# FPGAPower.net
KiCad netlist of a schematic drawn in Altium Designer
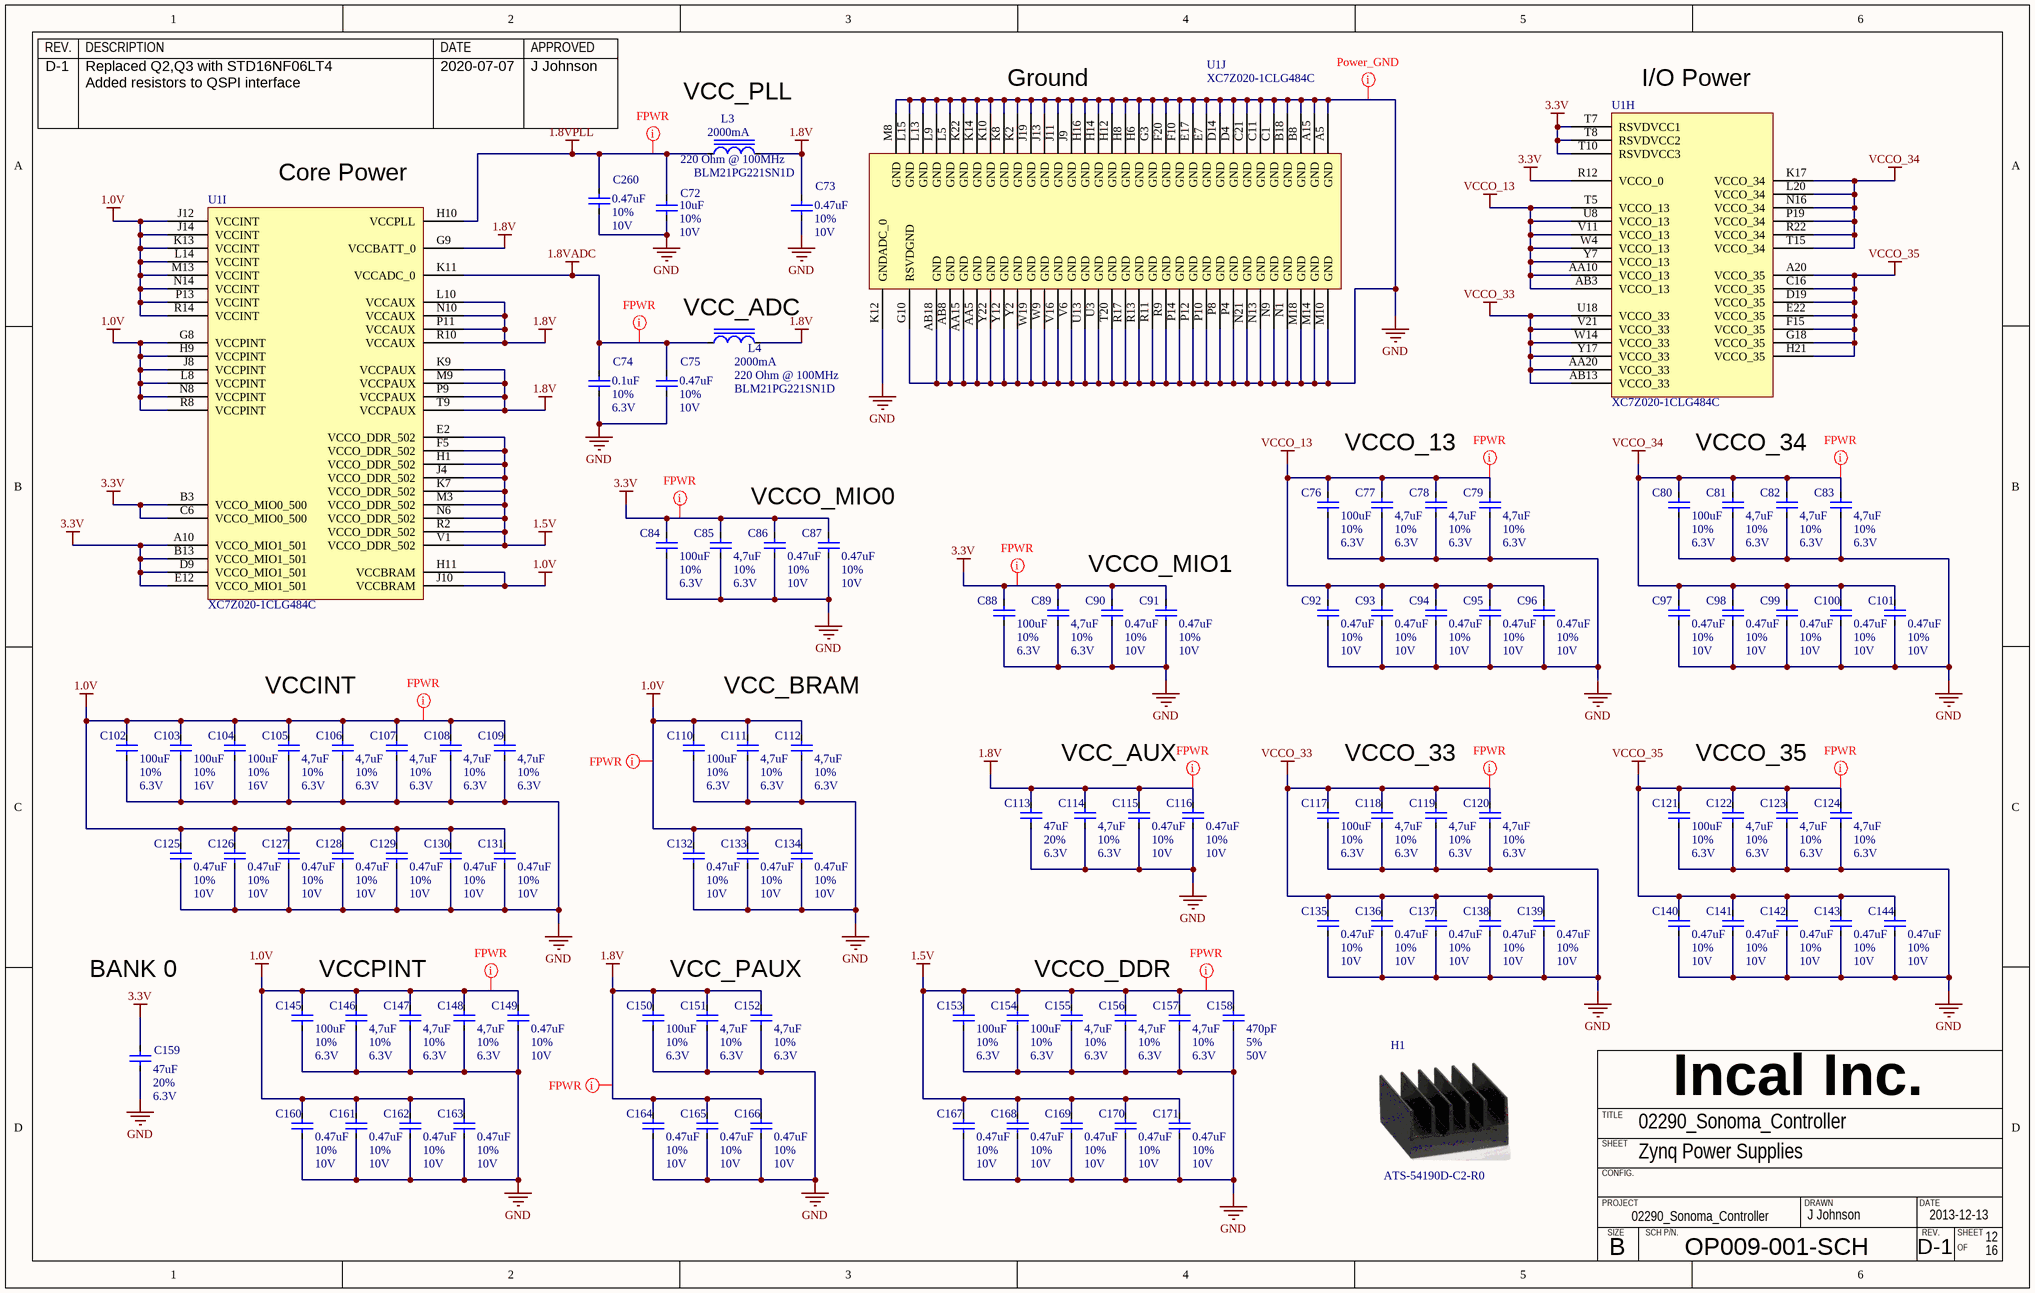
[diagram p0: FPGAPower.SchDoc]

(export (version "E")
  (design (tool "Eeschema 10.0.6"))
  (components
    (comp (ref "C72")
      (value "10uF")
      (footprint "CAPC1608X38N")
      (description "Capacitor ceramic, X5R, 10uF, 10V, 10%, -55 to +85 C, EIA0603")
      (fields
        (field (name "TOLERANCE") "10%")
        (field (name "VOLTAGE") "10V")
        (field (name "Comment") "CAPACITOR_NP_TYPE1")
      )
      (libsource (lib "parts") (part "CAPACITOR_NP_TYPE1"))
    )
    (comp (ref "C73")
      (value "0.47uF")
      (footprint "CAPC1005X55N")
      (description "Capacitor ceramic, X5R, 0.47uF, 10V, 10%, -55 to +85 C, EIA0402")
      (fields
        (field (name "TOLERANCE") "10%")
        (field (name "VOLTAGE") "10V")
        (field (name "Comment") "CAPACITOR_NP_TYPE1")
      )
      (libsource (lib "parts") (part "CAPACITOR_NP_TYPE1"))
    )
    (comp (ref "C74")
      (value "0.1uF")
      (footprint "CAPC0603X33N")
      (description "Capacitor ceramic, X5R, 0.1uF, 6.3V, 10%, -55 to +125 C, EIA0201")
      (fields
        (field (name "TOLERANCE") "10%")
        (field (name "VOLTAGE") "6.3V")
        (field (name "Comment") "CAPACITOR_NP_TYPE1")
      )
      (libsource (lib "parts") (part "CAPACITOR_NP_TYPE1"))
    )
    (comp (ref "C75")
      (value "0.47uF")
      (footprint "CAPC1005X55N")
      (description "Capacitor ceramic, X5R, 0.47uF, 10V, 10%, -55 to +85 C, EIA0402")
      (fields
        (field (name "TOLERANCE") "10%")
        (field (name "VOLTAGE") "10V")
        (field (name "Comment") "CAPACITOR_NP_TYPE1")
      )
      (libsource (lib "parts") (part "CAPACITOR_NP_TYPE1"))
    )
    (comp (ref "C76")
      (value "100uF")
      (footprint "CAPC3225X250N")
      (description "Capacitor ceramic, X5R, 100uF, 6.3V, 10%, -55 to +85 C, EIA1210")
      (fields
        (field (name "TOLERANCE") "10%")
        (field (name "VOLTAGE") "6.3V")
        (field (name "Comment") "CAPACITOR_NP_TYPE1")
      )
      (libsource (lib "parts") (part "CAPACITOR_NP_TYPE1"))
    )
    (comp (ref "C77")
      (value "4,7uF")
      (footprint "CAPC1005X33N")
      (description "Capacitor ceramic, X5R, 4,7uF, 6.3V, 10%, -55 to +85 C, EIA0402")
      (fields
        (field (name "TOLERANCE") "10%")
        (field (name "VOLTAGE") "6.3V")
        (field (name "Comment") "CAPACITOR_NP_TYPE1")
      )
      (libsource (lib "parts") (part "CAPACITOR_NP_TYPE1"))
    )
    (comp (ref "C78")
      (value "4,7uF")
      (footprint "CAPC1005X33N")
      (description "Capacitor ceramic, X5R, 4,7uF, 6.3V, 10%, -55 to +85 C, EIA0402")
      (fields
        (field (name "TOLERANCE") "10%")
        (field (name "VOLTAGE") "6.3V")
        (field (name "Comment") "CAPACITOR_NP_TYPE1")
      )
      (libsource (lib "parts") (part "CAPACITOR_NP_TYPE1"))
    )
    (comp (ref "C79")
      (value "4,7uF")
      (footprint "CAPC1005X33N")
      (description "Capacitor ceramic, X5R, 4,7uF, 6.3V, 10%, -55 to +85 C, EIA0402")
      (fields
        (field (name "TOLERANCE") "10%")
        (field (name "VOLTAGE") "6.3V")
        (field (name "Comment") "CAPACITOR_NP_TYPE1")
      )
      (libsource (lib "parts") (part "CAPACITOR_NP_TYPE1"))
    )
    (comp (ref "C80")
      (value "100uF")
      (footprint "CAPC3225X250N")
      (description "Capacitor ceramic, X5R, 100uF, 6.3V, 10%, -55 to +85 C, EIA1210")
      (fields
        (field (name "TOLERANCE") "10%")
        (field (name "VOLTAGE") "6.3V")
        (field (name "Comment") "CAPACITOR_NP_TYPE1")
      )
      (libsource (lib "parts") (part "CAPACITOR_NP_TYPE1"))
    )
    (comp (ref "C81")
      (value "4,7uF")
      (footprint "CAPC1005X33N")
      (description "Capacitor ceramic, X5R, 4,7uF, 6.3V, 10%, -55 to +85 C, EIA0402")
      (fields
        (field (name "TOLERANCE") "10%")
        (field (name "VOLTAGE") "6.3V")
        (field (name "Comment") "CAPACITOR_NP_TYPE1")
      )
      (libsource (lib "parts") (part "CAPACITOR_NP_TYPE1"))
    )
    (comp (ref "C82")
      (value "4,7uF")
      (footprint "CAPC1005X33N")
      (description "Capacitor ceramic, X5R, 4,7uF, 6.3V, 10%, -55 to +85 C, EIA0402")
      (fields
        (field (name "TOLERANCE") "10%")
        (field (name "VOLTAGE") "6.3V")
        (field (name "Comment") "CAPACITOR_NP_TYPE1")
      )
      (libsource (lib "parts") (part "CAPACITOR_NP_TYPE1"))
    )
    (comp (ref "C83")
      (value "4,7uF")
      (footprint "CAPC1005X33N")
      (description "Capacitor ceramic, X5R, 4,7uF, 6.3V, 10%, -55 to +85 C, EIA0402")
      (fields
        (field (name "TOLERANCE") "10%")
        (field (name "VOLTAGE") "6.3V")
        (field (name "Comment") "CAPACITOR_NP_TYPE1")
      )
      (libsource (lib "parts") (part "CAPACITOR_NP_TYPE1"))
    )
    (comp (ref "C84")
      (value "100uF")
      (footprint "CAPC3225X250N")
      (description "Capacitor ceramic, X5R, 100uF, 6.3V, 10%, -55 to +85 C, EIA1210")
      (fields
        (field (name "TOLERANCE") "10%")
        (field (name "VOLTAGE") "6.3V")
        (field (name "Comment") "CAPACITOR_NP_TYPE1")
      )
      (libsource (lib "parts") (part "CAPACITOR_NP_TYPE1"))
    )
    (comp (ref "C85")
      (value "4,7uF")
      (footprint "CAPC1005X33N")
      (description "Capacitor ceramic, X5R, 4,7uF, 6.3V, 10%, -55 to +85 C, EIA0402")
      (fields
        (field (name "TOLERANCE") "10%")
        (field (name "VOLTAGE") "6.3V")
        (field (name "Comment") "CAPACITOR_NP_TYPE1")
      )
      (libsource (lib "parts") (part "CAPACITOR_NP_TYPE1"))
    )
    (comp (ref "C86")
      (value "0.47uF")
      (footprint "CAPC1005X55N")
      (description "Capacitor ceramic, X5R, 0.47uF, 10V, 10%, -55 to +85 C, EIA0402")
      (fields
        (field (name "TOLERANCE") "10%")
        (field (name "VOLTAGE") "10V")
        (field (name "Comment") "CAPACITOR_NP_TYPE1")
      )
      (libsource (lib "parts") (part "CAPACITOR_NP_TYPE1"))
    )
    (comp (ref "C87")
      (value "0.47uF")
      (footprint "CAPC1005X55N")
      (description "Capacitor ceramic, X5R, 0.47uF, 10V, 10%, -55 to +85 C, EIA0402")
      (fields
        (field (name "TOLERANCE") "10%")
        (field (name "VOLTAGE") "10V")
        (field (name "Comment") "CAPACITOR_NP_TYPE1")
      )
      (libsource (lib "parts") (part "CAPACITOR_NP_TYPE1"))
    )
    (comp (ref "C88")
      (value "100uF")
      (footprint "CAPC3225X250N")
      (description "Capacitor ceramic, X5R, 100uF, 6.3V, 10%, -55 to +85 C, EIA1210")
      (fields
        (field (name "TOLERANCE") "10%")
        (field (name "VOLTAGE") "6.3V")
        (field (name "Comment") "CAPACITOR_NP_TYPE1")
      )
      (libsource (lib "parts") (part "CAPACITOR_NP_TYPE1"))
    )
    (comp (ref "C89")
      (value "4,7uF")
      (footprint "CAPC1005X33N")
      (description "Capacitor ceramic, X5R, 4,7uF, 6.3V, 10%, -55 to +85 C, EIA0402")
      (fields
        (field (name "TOLERANCE") "10%")
        (field (name "VOLTAGE") "6.3V")
        (field (name "Comment") "CAPACITOR_NP_TYPE1")
      )
      (libsource (lib "parts") (part "CAPACITOR_NP_TYPE1"))
    )
    (comp (ref "C90")
      (value "0.47uF")
      (footprint "CAPC1005X55N")
      (description "Capacitor ceramic, X5R, 0.47uF, 10V, 10%, -55 to +85 C, EIA0402")
      (fields
        (field (name "TOLERANCE") "10%")
        (field (name "VOLTAGE") "10V")
        (field (name "Comment") "CAPACITOR_NP_TYPE1")
      )
      (libsource (lib "parts") (part "CAPACITOR_NP_TYPE1"))
    )
    (comp (ref "C91")
      (value "0.47uF")
      (footprint "CAPC1005X55N")
      (description "Capacitor ceramic, X5R, 0.47uF, 10V, 10%, -55 to +85 C, EIA0402")
      (fields
        (field (name "TOLERANCE") "10%")
        (field (name "VOLTAGE") "10V")
        (field (name "Comment") "CAPACITOR_NP_TYPE1")
      )
      (libsource (lib "parts") (part "CAPACITOR_NP_TYPE1"))
    )
    (comp (ref "C92")
      (value "0.47uF")
      (footprint "CAPC1005X55N")
      (description "Capacitor ceramic, X5R, 0.47uF, 10V, 10%, -55 to +85 C, EIA0402")
      (fields
        (field (name "TOLERANCE") "10%")
        (field (name "VOLTAGE") "10V")
        (field (name "Comment") "CAPACITOR_NP_TYPE1")
      )
      (libsource (lib "parts") (part "CAPACITOR_NP_TYPE1"))
    )
    (comp (ref "C93")
      (value "0.47uF")
      (footprint "CAPC1005X55N")
      (description "Capacitor ceramic, X5R, 0.47uF, 10V, 10%, -55 to +85 C, EIA0402")
      (fields
        (field (name "TOLERANCE") "10%")
        (field (name "VOLTAGE") "10V")
        (field (name "Comment") "CAPACITOR_NP_TYPE1")
      )
      (libsource (lib "parts") (part "CAPACITOR_NP_TYPE1"))
    )
    (comp (ref "C94")
      (value "0.47uF")
      (footprint "CAPC1005X55N")
      (description "Capacitor ceramic, X5R, 0.47uF, 10V, 10%, -55 to +85 C, EIA0402")
      (fields
        (field (name "TOLERANCE") "10%")
        (field (name "VOLTAGE") "10V")
        (field (name "Comment") "CAPACITOR_NP_TYPE1")
      )
      (libsource (lib "parts") (part "CAPACITOR_NP_TYPE1"))
    )
    (comp (ref "C95")
      (value "0.47uF")
      (footprint "CAPC1005X55N")
      (description "Capacitor ceramic, X5R, 0.47uF, 10V, 10%, -55 to +85 C, EIA0402")
      (fields
        (field (name "TOLERANCE") "10%")
        (field (name "VOLTAGE") "10V")
        (field (name "Comment") "CAPACITOR_NP_TYPE1")
      )
      (libsource (lib "parts") (part "CAPACITOR_NP_TYPE1"))
    )
    (comp (ref "C96")
      (value "0.47uF")
      (footprint "CAPC1005X55N")
      (description "Capacitor ceramic, X5R, 0.47uF, 10V, 10%, -55 to +85 C, EIA0402")
      (fields
        (field (name "TOLERANCE") "10%")
        (field (name "VOLTAGE") "10V")
        (field (name "Comment") "CAPACITOR_NP_TYPE1")
      )
      (libsource (lib "parts") (part "CAPACITOR_NP_TYPE1"))
    )
    (comp (ref "C97")
      (value "0.47uF")
      (footprint "CAPC1005X55N")
      (description "Capacitor ceramic, X5R, 0.47uF, 10V, 10%, -55 to +85 C, EIA0402")
      (fields
        (field (name "TOLERANCE") "10%")
        (field (name "VOLTAGE") "10V")
        (field (name "Comment") "CAPACITOR_NP_TYPE1")
      )
      (libsource (lib "parts") (part "CAPACITOR_NP_TYPE1"))
    )
    (comp (ref "C98")
      (value "0.47uF")
      (footprint "CAPC1005X55N")
      (description "Capacitor ceramic, X5R, 0.47uF, 10V, 10%, -55 to +85 C, EIA0402")
      (fields
        (field (name "TOLERANCE") "10%")
        (field (name "VOLTAGE") "10V")
        (field (name "Comment") "CAPACITOR_NP_TYPE1")
      )
      (libsource (lib "parts") (part "CAPACITOR_NP_TYPE1"))
    )
    (comp (ref "C99")
      (value "0.47uF")
      (footprint "CAPC1005X55N")
      (description "Capacitor ceramic, X5R, 0.47uF, 10V, 10%, -55 to +85 C, EIA0402")
      (fields
        (field (name "TOLERANCE") "10%")
        (field (name "VOLTAGE") "10V")
        (field (name "Comment") "CAPACITOR_NP_TYPE1")
      )
      (libsource (lib "parts") (part "CAPACITOR_NP_TYPE1"))
    )
    (comp (ref "C100")
      (value "0.47uF")
      (footprint "CAPC1005X55N")
      (description "Capacitor ceramic, X5R, 0.47uF, 10V, 10%, -55 to +85 C, EIA0402")
      (fields
        (field (name "TOLERANCE") "10%")
        (field (name "VOLTAGE") "10V")
        (field (name "Comment") "CAPACITOR_NP_TYPE1")
      )
      (libsource (lib "parts") (part "CAPACITOR_NP_TYPE1"))
    )
    (comp (ref "C101")
      (value "0.47uF")
      (footprint "CAPC1005X55N")
      (description "Capacitor ceramic, X5R, 0.47uF, 10V, 10%, -55 to +85 C, EIA0402")
      (fields
        (field (name "TOLERANCE") "10%")
        (field (name "VOLTAGE") "10V")
        (field (name "Comment") "CAPACITOR_NP_TYPE1")
      )
      (libsource (lib "parts") (part "CAPACITOR_NP_TYPE1"))
    )
    (comp (ref "C102")
      (value "100uF")
      (footprint "CAPC3225X250N")
      (description "Capacitor ceramic, X5R, 100uF, 6.3V, 10%, -55 to +85 C, EIA1210")
      (fields
        (field (name "TOLERANCE") "10%")
        (field (name "VOLTAGE") "6.3V")
        (field (name "Comment") "CAPACITOR_NP_TYPE1")
      )
      (libsource (lib "parts") (part "CAPACITOR_NP_TYPE1"))
    )
    (comp (ref "C103")
      (value "100uF")
      (footprint "CAPC3225X250N")
      (description "Capacitor ceramic, X5R, 100uF, 16V, 10%, -55 to +85 C, EIA1210")
      (fields
        (field (name "TOLERANCE") "10%")
        (field (name "VOLTAGE") "16V")
        (field (name "Comment") "CAPACITOR_NP_TYPE1")
      )
      (libsource (lib "parts") (part "CAPACITOR_NP_TYPE1"))
    )
    (comp (ref "C104")
      (value "100uF")
      (footprint "CAPC3225X250N")
      (description "Capacitor ceramic, X5R, 100uF, 16V, 10%, -55 to +85 C, EIA1210")
      (fields
        (field (name "TOLERANCE") "10%")
        (field (name "VOLTAGE") "16V")
        (field (name "Comment") "CAPACITOR_NP_TYPE1")
      )
      (libsource (lib "parts") (part "CAPACITOR_NP_TYPE1"))
    )
    (comp (ref "C105")
      (value "4,7uF")
      (footprint "CAPC1005X33N")
      (description "Capacitor ceramic, X5R, 4,7uF, 6.3V, 10%, -55 to +85 C, EIA0402")
      (fields
        (field (name "TOLERANCE") "10%")
        (field (name "VOLTAGE") "6.3V")
        (field (name "Comment") "CAPACITOR_NP_TYPE1")
      )
      (libsource (lib "parts") (part "CAPACITOR_NP_TYPE1"))
    )
    (comp (ref "C106")
      (value "4,7uF")
      (footprint "CAPC1005X33N")
      (description "Capacitor ceramic, X5R, 4,7uF, 6.3V, 10%, -55 to +85 C, EIA0402")
      (fields
        (field (name "TOLERANCE") "10%")
        (field (name "VOLTAGE") "6.3V")
        (field (name "Comment") "CAPACITOR_NP_TYPE1")
      )
      (libsource (lib "parts") (part "CAPACITOR_NP_TYPE1"))
    )
    (comp (ref "C107")
      (value "4,7uF")
      (footprint "CAPC1005X33N")
      (description "Capacitor ceramic, X5R, 4,7uF, 6.3V, 10%, -55 to +85 C, EIA0402")
      (fields
        (field (name "TOLERANCE") "10%")
        (field (name "VOLTAGE") "6.3V")
        (field (name "Comment") "CAPACITOR_NP_TYPE1")
      )
      (libsource (lib "parts") (part "CAPACITOR_NP_TYPE1"))
    )
    (comp (ref "C108")
      (value "4,7uF")
      (footprint "CAPC1005X33N")
      (description "Capacitor ceramic, X5R, 4,7uF, 6.3V, 10%, -55 to +85 C, EIA0402")
      (fields
        (field (name "TOLERANCE") "10%")
        (field (name "VOLTAGE") "6.3V")
        (field (name "Comment") "CAPACITOR_NP_TYPE1")
      )
      (libsource (lib "parts") (part "CAPACITOR_NP_TYPE1"))
    )
    (comp (ref "C109")
      (value "4,7uF")
      (footprint "CAPC1005X33N")
      (description "Capacitor ceramic, X5R, 4,7uF, 6.3V, 10%, -55 to +85 C, EIA0402")
      (fields
        (field (name "TOLERANCE") "10%")
        (field (name "VOLTAGE") "6.3V")
        (field (name "Comment") "CAPACITOR_NP_TYPE1")
      )
      (libsource (lib "parts") (part "CAPACITOR_NP_TYPE1"))
    )
    (comp (ref "C110")
      (value "100uF")
      (footprint "CAPC3225X250N")
      (description "Capacitor ceramic, X5R, 100uF, 6.3V, 10%, -55 to +85 C, EIA1210")
      (fields
        (field (name "TOLERANCE") "10%")
        (field (name "VOLTAGE") "6.3V")
        (field (name "Comment") "CAPACITOR_NP_TYPE1")
      )
      (libsource (lib "parts") (part "CAPACITOR_NP_TYPE1"))
    )
    (comp (ref "C111")
      (value "4,7uF")
      (footprint "CAPC1005X33N")
      (description "Capacitor ceramic, X5R, 4,7uF, 6.3V, 10%, -55 to +85 C, EIA0402")
      (fields
        (field (name "TOLERANCE") "10%")
        (field (name "VOLTAGE") "6.3V")
        (field (name "Comment") "CAPACITOR_NP_TYPE1")
      )
      (libsource (lib "parts") (part "CAPACITOR_NP_TYPE1"))
    )
    (comp (ref "C112")
      (value "4,7uF")
      (footprint "CAPC1005X33N")
      (description "Capacitor ceramic, X5R, 4,7uF, 6.3V, 10%, -55 to +85 C, EIA0402")
      (fields
        (field (name "TOLERANCE") "10%")
        (field (name "VOLTAGE") "6.3V")
        (field (name "Comment") "CAPACITOR_NP_TYPE1")
      )
      (libsource (lib "parts") (part "CAPACITOR_NP_TYPE1"))
    )
    (comp (ref "C113")
      (value "47uF")
      (footprint "CAPC2013X125N")
      (description "Capacitor ceramic, X5R, 47uF, 6.3V, 20%, -55 to +85 C,")
      (fields
        (field (name "TOLERANCE") "20%")
        (field (name "VOLTAGE") "6.3V")
        (field (name "Comment") "CAPACITOR_NP_TYPE1")
      )
      (libsource (lib "parts") (part "CAPACITOR_NP_TYPE1"))
    )
    (comp (ref "C114")
      (value "4,7uF")
      (footprint "CAPC1005X33N")
      (description "Capacitor ceramic, X5R, 4,7uF, 6.3V, 10%, -55 to +85 C, EIA0402")
      (fields
        (field (name "TOLERANCE") "10%")
        (field (name "VOLTAGE") "6.3V")
        (field (name "Comment") "CAPACITOR_NP_TYPE1")
      )
      (libsource (lib "parts") (part "CAPACITOR_NP_TYPE1"))
    )
    (comp (ref "C115")
      (value "0.47uF")
      (footprint "CAPC1005X55N")
      (description "Capacitor ceramic, X5R, 0.47uF, 10V, 10%, -55 to +85 C, EIA0402")
      (fields
        (field (name "TOLERANCE") "10%")
        (field (name "VOLTAGE") "10V")
        (field (name "Comment") "CAPACITOR_NP_TYPE1")
      )
      (libsource (lib "parts") (part "CAPACITOR_NP_TYPE1"))
    )
    (comp (ref "C116")
      (value "0.47uF")
      (footprint "CAPC1005X55N")
      (description "Capacitor ceramic, X5R, 0.47uF, 10V, 10%, -55 to +85 C, EIA0402")
      (fields
        (field (name "TOLERANCE") "10%")
        (field (name "VOLTAGE") "10V")
        (field (name "Comment") "CAPACITOR_NP_TYPE1")
      )
      (libsource (lib "parts") (part "CAPACITOR_NP_TYPE1"))
    )
    (comp (ref "C117")
      (value "100uF")
      (footprint "CAPC3225X250N")
      (description "Capacitor ceramic, X5R, 100uF, 6.3V, 10%, -55 to +85 C, EIA1210")
      (fields
        (field (name "TOLERANCE") "10%")
        (field (name "VOLTAGE") "6.3V")
        (field (name "Comment") "CAPACITOR_NP_TYPE1")
      )
      (libsource (lib "parts") (part "CAPACITOR_NP_TYPE1"))
    )
    (comp (ref "C118")
      (value "4,7uF")
      (footprint "CAPC1005X33N")
      (description "Capacitor ceramic, X5R, 4,7uF, 6.3V, 10%, -55 to +85 C, EIA0402")
      (fields
        (field (name "TOLERANCE") "10%")
        (field (name "VOLTAGE") "6.3V")
        (field (name "Comment") "CAPACITOR_NP_TYPE1")
      )
      (libsource (lib "parts") (part "CAPACITOR_NP_TYPE1"))
    )
    (comp (ref "C119")
      (value "4,7uF")
      (footprint "CAPC1005X33N")
      (description "Capacitor ceramic, X5R, 4,7uF, 6.3V, 10%, -55 to +85 C, EIA0402")
      (fields
        (field (name "TOLERANCE") "10%")
        (field (name "VOLTAGE") "6.3V")
        (field (name "Comment") "CAPACITOR_NP_TYPE1")
      )
      (libsource (lib "parts") (part "CAPACITOR_NP_TYPE1"))
    )
    (comp (ref "C120")
      (value "4,7uF")
      (footprint "CAPC1005X33N")
      (description "Capacitor ceramic, X5R, 4,7uF, 6.3V, 10%, -55 to +85 C, EIA0402")
      (fields
        (field (name "TOLERANCE") "10%")
        (field (name "VOLTAGE") "6.3V")
        (field (name "Comment") "CAPACITOR_NP_TYPE1")
      )
      (libsource (lib "parts") (part "CAPACITOR_NP_TYPE1"))
    )
    (comp (ref "C121")
      (value "100uF")
      (footprint "CAPC3225X250N")
      (description "Capacitor ceramic, X5R, 100uF, 6.3V, 10%, -55 to +85 C, EIA1210")
      (fields
        (field (name "TOLERANCE") "10%")
        (field (name "VOLTAGE") "6.3V")
        (field (name "Comment") "CAPACITOR_NP_TYPE1")
      )
      (libsource (lib "parts") (part "CAPACITOR_NP_TYPE1"))
    )
    (comp (ref "C122")
      (value "4,7uF")
      (footprint "CAPC1005X33N")
      (description "Capacitor ceramic, X5R, 4,7uF, 6.3V, 10%, -55 to +85 C, EIA0402")
      (fields
        (field (name "TOLERANCE") "10%")
        (field (name "VOLTAGE") "6.3V")
        (field (name "Comment") "CAPACITOR_NP_TYPE1")
      )
      (libsource (lib "parts") (part "CAPACITOR_NP_TYPE1"))
    )
    (comp (ref "C123")
      (value "4,7uF")
      (footprint "CAPC1005X33N")
      (description "Capacitor ceramic, X5R, 4,7uF, 6.3V, 10%, -55 to +85 C, EIA0402")
      (fields
        (field (name "TOLERANCE") "10%")
        (field (name "VOLTAGE") "6.3V")
        (field (name "Comment") "CAPACITOR_NP_TYPE1")
      )
      (libsource (lib "parts") (part "CAPACITOR_NP_TYPE1"))
    )
    (comp (ref "C124")
      (value "4,7uF")
      (footprint "CAPC1005X33N")
      (description "Capacitor ceramic, X5R, 4,7uF, 6.3V, 10%, -55 to +85 C, EIA0402")
      (fields
        (field (name "TOLERANCE") "10%")
        (field (name "VOLTAGE") "6.3V")
        (field (name "Comment") "CAPACITOR_NP_TYPE1")
      )
      (libsource (lib "parts") (part "CAPACITOR_NP_TYPE1"))
    )
    (comp (ref "C125")
      (value "0.47uF")
      (footprint "CAPC1005X55N")
      (description "Capacitor ceramic, X5R, 0.47uF, 10V, 10%, -55 to +85 C, EIA0402")
      (fields
        (field (name "TOLERANCE") "10%")
        (field (name "VOLTAGE") "10V")
        (field (name "Comment") "CAPACITOR_NP_TYPE1")
      )
      (libsource (lib "parts") (part "CAPACITOR_NP_TYPE1"))
    )
    (comp (ref "C126")
      (value "0.47uF")
      (footprint "CAPC1005X55N")
      (description "Capacitor ceramic, X5R, 0.47uF, 10V, 10%, -55 to +85 C, EIA0402")
      (fields
        (field (name "TOLERANCE") "10%")
        (field (name "VOLTAGE") "10V")
        (field (name "Comment") "CAPACITOR_NP_TYPE1")
      )
      (libsource (lib "parts") (part "CAPACITOR_NP_TYPE1"))
    )
    (comp (ref "C127")
      (value "0.47uF")
      (footprint "CAPC1005X55N")
      (description "Capacitor ceramic, X5R, 0.47uF, 10V, 10%, -55 to +85 C, EIA0402")
      (fields
        (field (name "TOLERANCE") "10%")
        (field (name "VOLTAGE") "10V")
        (field (name "Comment") "CAPACITOR_NP_TYPE1")
      )
      (libsource (lib "parts") (part "CAPACITOR_NP_TYPE1"))
    )
    (comp (ref "C128")
      (value "0.47uF")
      (footprint "CAPC1005X55N")
      (description "Capacitor ceramic, X5R, 0.47uF, 10V, 10%, -55 to +85 C, EIA0402")
      (fields
        (field (name "TOLERANCE") "10%")
        (field (name "VOLTAGE") "10V")
        (field (name "Comment") "CAPACITOR_NP_TYPE1")
      )
      (libsource (lib "parts") (part "CAPACITOR_NP_TYPE1"))
    )
    (comp (ref "C129")
      (value "0.47uF")
      (footprint "CAPC1005X55N")
      (description "Capacitor ceramic, X5R, 0.47uF, 10V, 10%, -55 to +85 C, EIA0402")
      (fields
        (field (name "TOLERANCE") "10%")
        (field (name "VOLTAGE") "10V")
        (field (name "Comment") "CAPACITOR_NP_TYPE1")
      )
      (libsource (lib "parts") (part "CAPACITOR_NP_TYPE1"))
    )
    (comp (ref "C130")
      (value "0.47uF")
      (footprint "CAPC1005X55N")
      (description "Capacitor ceramic, X5R, 0.47uF, 10V, 10%, -55 to +85 C, EIA0402")
      (fields
        (field (name "TOLERANCE") "10%")
        (field (name "VOLTAGE") "10V")
        (field (name "Comment") "CAPACITOR_NP_TYPE1")
      )
      (libsource (lib "parts") (part "CAPACITOR_NP_TYPE1"))
    )
    (comp (ref "C131")
      (value "0.47uF")
      (footprint "CAPC1005X55N")
      (description "Capacitor ceramic, X5R, 0.47uF, 10V, 10%, -55 to +85 C, EIA0402")
      (fields
        (field (name "TOLERANCE") "10%")
        (field (name "VOLTAGE") "10V")
        (field (name "Comment") "CAPACITOR_NP_TYPE1")
      )
      (libsource (lib "parts") (part "CAPACITOR_NP_TYPE1"))
    )
    (comp (ref "C132")
      (value "0.47uF")
      (footprint "CAPC1005X55N")
      (description "Capacitor ceramic, X5R, 0.47uF, 10V, 10%, -55 to +85 C, EIA0402")
      (fields
        (field (name "TOLERANCE") "10%")
        (field (name "VOLTAGE") "10V")
        (field (name "Comment") "CAPACITOR_NP_TYPE1")
      )
      (libsource (lib "parts") (part "CAPACITOR_NP_TYPE1"))
    )
    (comp (ref "C133")
      (value "0.47uF")
      (footprint "CAPC1005X55N")
      (description "Capacitor ceramic, X5R, 0.47uF, 10V, 10%, -55 to +85 C, EIA0402")
      (fields
        (field (name "TOLERANCE") "10%")
        (field (name "VOLTAGE") "10V")
        (field (name "Comment") "CAPACITOR_NP_TYPE1")
      )
      (libsource (lib "parts") (part "CAPACITOR_NP_TYPE1"))
    )
    (comp (ref "C134")
      (value "0.47uF")
      (footprint "CAPC1005X55N")
      (description "Capacitor ceramic, X5R, 0.47uF, 10V, 10%, -55 to +85 C, EIA0402")
      (fields
        (field (name "TOLERANCE") "10%")
        (field (name "VOLTAGE") "10V")
        (field (name "Comment") "CAPACITOR_NP_TYPE1")
      )
      (libsource (lib "parts") (part "CAPACITOR_NP_TYPE1"))
    )
    (comp (ref "C135")
      (value "0.47uF")
      (footprint "CAPC1005X55N")
      (description "Capacitor ceramic, X5R, 0.47uF, 10V, 10%, -55 to +85 C, EIA0402")
      (fields
        (field (name "TOLERANCE") "10%")
        (field (name "VOLTAGE") "10V")
        (field (name "Comment") "CAPACITOR_NP_TYPE1")
      )
      (libsource (lib "parts") (part "CAPACITOR_NP_TYPE1"))
    )
    (comp (ref "C136")
      (value "0.47uF")
      (footprint "CAPC1005X55N")
      (description "Capacitor ceramic, X5R, 0.47uF, 10V, 10%, -55 to +85 C, EIA0402")
      (fields
        (field (name "TOLERANCE") "10%")
        (field (name "VOLTAGE") "10V")
        (field (name "Comment") "CAPACITOR_NP_TYPE1")
      )
      (libsource (lib "parts") (part "CAPACITOR_NP_TYPE1"))
    )
    (comp (ref "C137")
      (value "0.47uF")
      (footprint "CAPC1005X55N")
      (description "Capacitor ceramic, X5R, 0.47uF, 10V, 10%, -55 to +85 C, EIA0402")
      (fields
        (field (name "TOLERANCE") "10%")
        (field (name "VOLTAGE") "10V")
        (field (name "Comment") "CAPACITOR_NP_TYPE1")
      )
      (libsource (lib "parts") (part "CAPACITOR_NP_TYPE1"))
    )
    (comp (ref "C138")
      (value "0.47uF")
      (footprint "CAPC1005X55N")
      (description "Capacitor ceramic, X5R, 0.47uF, 10V, 10%, -55 to +85 C, EIA0402")
      (fields
        (field (name "TOLERANCE") "10%")
        (field (name "VOLTAGE") "10V")
        (field (name "Comment") "CAPACITOR_NP_TYPE1")
      )
      (libsource (lib "parts") (part "CAPACITOR_NP_TYPE1"))
    )
    (comp (ref "C139")
      (value "0.47uF")
      (footprint "CAPC1005X55N")
      (description "Capacitor ceramic, X5R, 0.47uF, 10V, 10%, -55 to +85 C, EIA0402")
      (fields
        (field (name "TOLERANCE") "10%")
        (field (name "VOLTAGE") "10V")
        (field (name "Comment") "CAPACITOR_NP_TYPE1")
      )
      (libsource (lib "parts") (part "CAPACITOR_NP_TYPE1"))
    )
    (comp (ref "C140")
      (value "0.47uF")
      (footprint "CAPC1005X55N")
      (description "Capacitor ceramic, X5R, 0.47uF, 10V, 10%, -55 to +85 C, EIA0402")
      (fields
        (field (name "TOLERANCE") "10%")
        (field (name "VOLTAGE") "10V")
        (field (name "Comment") "CAPACITOR_NP_TYPE1")
      )
      (libsource (lib "parts") (part "CAPACITOR_NP_TYPE1"))
    )
    (comp (ref "C141")
      (value "0.47uF")
      (footprint "CAPC1005X55N")
      (description "Capacitor ceramic, X5R, 0.47uF, 10V, 10%, -55 to +85 C, EIA0402")
      (fields
        (field (name "TOLERANCE") "10%")
        (field (name "VOLTAGE") "10V")
        (field (name "Comment") "CAPACITOR_NP_TYPE1")
      )
      (libsource (lib "parts") (part "CAPACITOR_NP_TYPE1"))
    )
    (comp (ref "C142")
      (value "0.47uF")
      (footprint "CAPC1005X55N")
      (description "Capacitor ceramic, X5R, 0.47uF, 10V, 10%, -55 to +85 C, EIA0402")
      (fields
        (field (name "TOLERANCE") "10%")
        (field (name "VOLTAGE") "10V")
        (field (name "Comment") "CAPACITOR_NP_TYPE1")
      )
      (libsource (lib "parts") (part "CAPACITOR_NP_TYPE1"))
    )
    (comp (ref "C143")
      (value "0.47uF")
      (footprint "CAPC1005X55N")
      (description "Capacitor ceramic, X5R, 0.47uF, 10V, 10%, -55 to +85 C, EIA0402")
      (fields
        (field (name "TOLERANCE") "10%")
        (field (name "VOLTAGE") "10V")
        (field (name "Comment") "CAPACITOR_NP_TYPE1")
      )
      (libsource (lib "parts") (part "CAPACITOR_NP_TYPE1"))
    )
    (comp (ref "C144")
      (value "0.47uF")
      (footprint "CAPC1005X55N")
      (description "Capacitor ceramic, X5R, 0.47uF, 10V, 10%, -55 to +85 C, EIA0402")
      (fields
        (field (name "TOLERANCE") "10%")
        (field (name "VOLTAGE") "10V")
        (field (name "Comment") "CAPACITOR_NP_TYPE1")
      )
      (libsource (lib "parts") (part "CAPACITOR_NP_TYPE1"))
    )
    (comp (ref "C145")
      (value "100uF")
      (footprint "CAPC3225X250N")
      (description "Capacitor ceramic, X5R, 100uF, 6.3V, 10%, -55 to +85 C, EIA1210")
      (fields
        (field (name "TOLERANCE") "10%")
        (field (name "VOLTAGE") "6.3V")
        (field (name "Comment") "CAPACITOR_NP_TYPE1")
      )
      (libsource (lib "parts") (part "CAPACITOR_NP_TYPE1"))
    )
    (comp (ref "C146")
      (value "4,7uF")
      (footprint "CAPC1005X33N")
      (description "Capacitor ceramic, X5R, 4,7uF, 6.3V, 10%, -55 to +85 C, EIA0402")
      (fields
        (field (name "TOLERANCE") "10%")
        (field (name "VOLTAGE") "6.3V")
        (field (name "Comment") "CAPACITOR_NP_TYPE1")
      )
      (libsource (lib "parts") (part "CAPACITOR_NP_TYPE1"))
    )
    (comp (ref "C147")
      (value "4,7uF")
      (footprint "CAPC1005X33N")
      (description "Capacitor ceramic, X5R, 4,7uF, 6.3V, 10%, -55 to +85 C, EIA0402")
      (fields
        (field (name "TOLERANCE") "10%")
        (field (name "VOLTAGE") "6.3V")
        (field (name "Comment") "CAPACITOR_NP_TYPE1")
      )
      (libsource (lib "parts") (part "CAPACITOR_NP_TYPE1"))
    )
    (comp (ref "C148")
      (value "4,7uF")
      (footprint "CAPC1005X33N")
      (description "Capacitor ceramic, X5R, 4,7uF, 6.3V, 10%, -55 to +85 C, EIA0402")
      (fields
        (field (name "TOLERANCE") "10%")
        (field (name "VOLTAGE") "6.3V")
        (field (name "Comment") "CAPACITOR_NP_TYPE1")
      )
      (libsource (lib "parts") (part "CAPACITOR_NP_TYPE1"))
    )
    (comp (ref "C149")
      (value "0.47uF")
      (footprint "CAPC1005X55N")
      (description "Capacitor ceramic, X5R, 0.47uF, 10V, 10%, -55 to +85 C, EIA0402")
      (fields
        (field (name "TOLERANCE") "10%")
        (field (name "VOLTAGE") "10V")
        (field (name "Comment") "CAPACITOR_NP_TYPE1")
      )
      (libsource (lib "parts") (part "CAPACITOR_NP_TYPE1"))
    )
    (comp (ref "C150")
      (value "100uF")
      (footprint "CAPC3225X250N")
      (description "Capacitor ceramic, X5R, 100uF, 6.3V, 10%, -55 to +85 C, EIA1210")
      (fields
        (field (name "TOLERANCE") "10%")
        (field (name "VOLTAGE") "6.3V")
        (field (name "Comment") "CAPACITOR_NP_TYPE1")
      )
      (libsource (lib "parts") (part "CAPACITOR_NP_TYPE1"))
    )
    (comp (ref "C151")
      (value "4,7uF")
      (footprint "CAPC1005X33N")
      (description "Capacitor ceramic, X5R, 4,7uF, 6.3V, 10%, -55 to +85 C, EIA0402")
      (fields
        (field (name "TOLERANCE") "10%")
        (field (name "VOLTAGE") "6.3V")
        (field (name "Comment") "CAPACITOR_NP_TYPE1")
      )
      (libsource (lib "parts") (part "CAPACITOR_NP_TYPE1"))
    )
    (comp (ref "C152")
      (value "4,7uF")
      (footprint "CAPC1005X33N")
      (description "Capacitor ceramic, X5R, 4,7uF, 6.3V, 10%, -55 to +85 C, EIA0402")
      (fields
        (field (name "TOLERANCE") "10%")
        (field (name "VOLTAGE") "6.3V")
        (field (name "Comment") "CAPACITOR_NP_TYPE1")
      )
      (libsource (lib "parts") (part "CAPACITOR_NP_TYPE1"))
    )
    (comp (ref "C153")
      (value "100uF")
      (footprint "CAPC3225X250N")
      (description "Capacitor ceramic, X5R, 100uF, 6.3V, 10%, -55 to +85 C, EIA1210")
      (fields
        (field (name "TOLERANCE") "10%")
        (field (name "VOLTAGE") "6.3V")
        (field (name "Comment") "CAPACITOR_NP_TYPE1")
      )
      (libsource (lib "parts") (part "CAPACITOR_NP_TYPE1"))
    )
    (comp (ref "C154")
      (value "100uF")
      (footprint "CAPC3225X250N")
      (description "Capacitor ceramic, X5R, 100uF, 6.3V, 10%, -55 to +85 C, EIA1210")
      (fields
        (field (name "TOLERANCE") "10%")
        (field (name "VOLTAGE") "6.3V")
        (field (name "Comment") "CAPACITOR_NP_TYPE1")
      )
      (libsource (lib "parts") (part "CAPACITOR_NP_TYPE1"))
    )
    (comp (ref "C155")
      (value "4,7uF")
      (footprint "CAPC1005X33N")
      (description "Capacitor ceramic, X5R, 4,7uF, 6.3V, 10%, -55 to +85 C, EIA0402")
      (fields
        (field (name "TOLERANCE") "10%")
        (field (name "VOLTAGE") "6.3V")
        (field (name "Comment") "CAPACITOR_NP_TYPE1")
      )
      (libsource (lib "parts") (part "CAPACITOR_NP_TYPE1"))
    )
    (comp (ref "C156")
      (value "4,7uF")
      (footprint "CAPC1005X33N")
      (description "Capacitor ceramic, X5R, 4,7uF, 6.3V, 10%, -55 to +85 C, EIA0402")
      (fields
        (field (name "TOLERANCE") "10%")
        (field (name "VOLTAGE") "6.3V")
        (field (name "Comment") "CAPACITOR_NP_TYPE1")
      )
      (libsource (lib "parts") (part "CAPACITOR_NP_TYPE1"))
    )
    (comp (ref "C157")
      (value "4,7uF")
      (footprint "CAPC1005X33N")
      (description "Capacitor ceramic, X5R, 4,7uF, 6.3V, 10%, -55 to +85 C, EIA0402")
      (fields
        (field (name "TOLERANCE") "10%")
        (field (name "VOLTAGE") "6.3V")
        (field (name "Comment") "CAPACITOR_NP_TYPE1")
      )
      (libsource (lib "parts") (part "CAPACITOR_NP_TYPE1"))
    )
    (comp (ref "C158")
      (value "470pF")
      (footprint "CAPC1005X33N")
      (description "Capacitor ceramic, C0G (NP0), 470pF, 50V, 5%, -55 to +125 C, EIA0402")
      (fields
        (field (name "TOLERANCE") "5%")
        (field (name "VOLTAGE") "50V")
        (field (name "Comment") "CAPACITOR_NP_TYPE1")
      )
      (libsource (lib "parts") (part "CAPACITOR_NP_TYPE1"))
    )
    (comp (ref "C159")
      (value "47uF")
      (footprint "CAPC2013X125N")
      (description "Capacitor ceramic, X5R, 47uF, 6.3V, 20%, -55 to +85 C,")
      (fields
        (field (name "TOLERANCE") "20%")
        (field (name "VOLTAGE") "6.3V")
        (field (name "Comment") "CAPACITOR_NP_TYPE1")
      )
      (libsource (lib "parts") (part "CAPACITOR_NP_TYPE1"))
    )
    (comp (ref "C160")
      (value "0.47uF")
      (footprint "CAPC1005X55N")
      (description "Capacitor ceramic, X5R, 0.47uF, 10V, 10%, -55 to +85 C, EIA0402")
      (fields
        (field (name "TOLERANCE") "10%")
        (field (name "VOLTAGE") "10V")
        (field (name "Comment") "CAPACITOR_NP_TYPE1")
      )
      (libsource (lib "parts") (part "CAPACITOR_NP_TYPE1"))
    )
    (comp (ref "C161")
      (value "0.47uF")
      (footprint "CAPC1005X55N")
      (description "Capacitor ceramic, X5R, 0.47uF, 10V, 10%, -55 to +85 C, EIA0402")
      (fields
        (field (name "TOLERANCE") "10%")
        (field (name "VOLTAGE") "10V")
        (field (name "Comment") "CAPACITOR_NP_TYPE1")
      )
      (libsource (lib "parts") (part "CAPACITOR_NP_TYPE1"))
    )
    (comp (ref "C162")
      (value "0.47uF")
      (footprint "CAPC1005X55N")
      (description "Capacitor ceramic, X5R, 0.47uF, 10V, 10%, -55 to +85 C, EIA0402")
      (fields
        (field (name "TOLERANCE") "10%")
        (field (name "VOLTAGE") "10V")
        (field (name "Comment") "CAPACITOR_NP_TYPE1")
      )
      (libsource (lib "parts") (part "CAPACITOR_NP_TYPE1"))
    )
    (comp (ref "C163")
      (value "0.47uF")
      (footprint "CAPC1005X55N")
      (description "Capacitor ceramic, X5R, 0.47uF, 10V, 10%, -55 to +85 C, EIA0402")
      (fields
        (field (name "TOLERANCE") "10%")
        (field (name "VOLTAGE") "10V")
        (field (name "Comment") "CAPACITOR_NP_TYPE1")
      )
      (libsource (lib "parts") (part "CAPACITOR_NP_TYPE1"))
    )
    (comp (ref "C164")
      (value "0.47uF")
      (footprint "CAPC1005X55N")
      (description "Capacitor ceramic, X5R, 0.47uF, 10V, 10%, -55 to +85 C, EIA0402")
      (fields
        (field (name "TOLERANCE") "10%")
        (field (name "VOLTAGE") "10V")
        (field (name "Comment") "CAPACITOR_NP_TYPE1")
      )
      (libsource (lib "parts") (part "CAPACITOR_NP_TYPE1"))
    )
    (comp (ref "C165")
      (value "0.47uF")
      (footprint "CAPC1005X55N")
      (description "Capacitor ceramic, X5R, 0.47uF, 10V, 10%, -55 to +85 C, EIA0402")
      (fields
        (field (name "TOLERANCE") "10%")
        (field (name "VOLTAGE") "10V")
        (field (name "Comment") "CAPACITOR_NP_TYPE1")
      )
      (libsource (lib "parts") (part "CAPACITOR_NP_TYPE1"))
    )
    (comp (ref "C166")
      (value "0.47uF")
      (footprint "CAPC1005X55N")
      (description "Capacitor ceramic, X5R, 0.47uF, 10V, 10%, -55 to +85 C, EIA0402")
      (fields
        (field (name "TOLERANCE") "10%")
        (field (name "VOLTAGE") "10V")
        (field (name "Comment") "CAPACITOR_NP_TYPE1")
      )
      (libsource (lib "parts") (part "CAPACITOR_NP_TYPE1"))
    )
    (comp (ref "C167")
      (value "0.47uF")
      (footprint "CAPC1005X55N")
      (description "Capacitor ceramic, X5R, 0.47uF, 10V, 10%, -55 to +85 C, EIA0402")
      (fields
        (field (name "TOLERANCE") "10%")
        (field (name "VOLTAGE") "10V")
        (field (name "Comment") "CAPACITOR_NP_TYPE1")
      )
      (libsource (lib "parts") (part "CAPACITOR_NP_TYPE1"))
    )
    (comp (ref "C168")
      (value "0.47uF")
      (footprint "CAPC1005X55N")
      (description "Capacitor ceramic, X5R, 0.47uF, 10V, 10%, -55 to +85 C, EIA0402")
      (fields
        (field (name "TOLERANCE") "10%")
        (field (name "VOLTAGE") "10V")
        (field (name "Comment") "CAPACITOR_NP_TYPE1")
      )
      (libsource (lib "parts") (part "CAPACITOR_NP_TYPE1"))
    )
    (comp (ref "C169")
      (value "0.47uF")
      (footprint "CAPC1005X55N")
      (description "Capacitor ceramic, X5R, 0.47uF, 10V, 10%, -55 to +85 C, EIA0402")
      (fields
        (field (name "TOLERANCE") "10%")
        (field (name "VOLTAGE") "10V")
        (field (name "Comment") "CAPACITOR_NP_TYPE1")
      )
      (libsource (lib "parts") (part "CAPACITOR_NP_TYPE1"))
    )
    (comp (ref "C170")
      (value "0.47uF")
      (footprint "CAPC1005X55N")
      (description "Capacitor ceramic, X5R, 0.47uF, 10V, 10%, -55 to +85 C, EIA0402")
      (fields
        (field (name "TOLERANCE") "10%")
        (field (name "VOLTAGE") "10V")
        (field (name "Comment") "CAPACITOR_NP_TYPE1")
      )
      (libsource (lib "parts") (part "CAPACITOR_NP_TYPE1"))
    )
    (comp (ref "C171")
      (value "0.47uF")
      (footprint "CAPC1005X55N")
      (description "Capacitor ceramic, X5R, 0.47uF, 10V, 10%, -55 to +85 C, EIA0402")
      (fields
        (field (name "TOLERANCE") "10%")
        (field (name "VOLTAGE") "10V")
        (field (name "Comment") "CAPACITOR_NP_TYPE1")
      )
      (libsource (lib "parts") (part "CAPACITOR_NP_TYPE1"))
    )
    (comp (ref "C260")
      (value "0.47uF")
      (footprint "CAPC1005X55N")
      (description "Capacitor ceramic, X5R, 0.47uF, 10V, 10%, -55 to +85 C, EIA0402")
      (fields
        (field (name "TOLERANCE") "10%")
        (field (name "VOLTAGE") "10V")
        (field (name "Comment") "CAPACITOR_NP_TYPE1")
      )
      (libsource (lib "parts") (part "CAPACITOR_NP_TYPE1"))
    )
    (comp (ref "H1")
      (value "ATS-54190D-C2-R0")
      (description "Heat Sink BGA, 19x19x9.5mm, Adhesive")
      (fields
        (field (name "POWER") "Pow")
        (field (name "VOLTAGE") "Vol")
        (field (name "MFG PART NUMBER 1") "ATS-54190D-C2-R0")
      )
      (libsource (lib "parts") (part "ATS-54190D-C2-R0"))
    )
    (comp (ref "L3")
      (value "220 Ohm @ 100MHz")
      (footprint "INDC2012X85N")
      (description "Ferrite chip, 220 Ohm @ 100MHz, 2000mA, 25%, -55 to +125 C, 0805")
      (fields
        (field (name "TOLERANCE") "25%")
        (field (name "CURRENT") "2000mA")
        (field (name "MFG PART NUMBER 1") "BLM21PG221SN1D")
        (field (name "Comment") "INDUCTOR_CORE_TYPE1")
      )
      (libsource (lib "parts") (part "INDUCTOR_CORE_TYPE1"))
    )
    (comp (ref "L4")
      (value "220 Ohm @ 100MHz")
      (footprint "INDC2012X85N")
      (description "Ferrite chip, 220 Ohm @ 100MHz, 2000mA, 25%, -55 to +125 C, 0805")
      (fields
        (field (name "TOLERANCE") "25%")
        (field (name "CURRENT") "2000mA")
        (field (name "MFG PART NUMBER 1") "BLM21PG221SN1D")
        (field (name "Comment") "INDUCTOR_CORE_TYPE1")
      )
      (libsource (lib "parts") (part "INDUCTOR_CORE_TYPE1"))
    )
    (comp (ref "U1")
      (value "XC7Z020-1CLG484C")
      (footprint "CLG484")
      (description "667 MHz Zynq™-7000 AP SoC, 130 PS I/O, 200 FPGA I/O, 484-Ball BGA, Speed Grade 1, Commercial Grade")
      (fields (field (name "GENERIC PART NUMBER") "XC7Z020") (field (name "MANUFACTURER") "Xilinx"))
      (libsource (lib "") (part "XC7Z020-1CLG484C_1"))
    )
  )
  (nets
    (net (code "1") (name "1.0V") (class "Default")
      (node (ref "C102") (pin "1") (pinfunction "1_1") (pintype "passive"))
      (node (ref "C103") (pin "1") (pinfunction "1_1") (pintype "passive"))
      (node (ref "C104") (pin "1") (pinfunction "1_1") (pintype "passive"))
      (node (ref "C105") (pin "1") (pinfunction "1_1") (pintype "passive"))
      (node (ref "C106") (pin "1") (pinfunction "1_1") (pintype "passive"))
      (node (ref "C107") (pin "1") (pinfunction "1_1") (pintype "passive"))
      (node (ref "C108") (pin "1") (pinfunction "1_1") (pintype "passive"))
      (node (ref "C109") (pin "1") (pinfunction "1_1") (pintype "passive"))
      (node (ref "C110") (pin "1") (pinfunction "1_1") (pintype "passive"))
      (node (ref "C111") (pin "1") (pinfunction "1_1") (pintype "passive"))
      (node (ref "C112") (pin "1") (pinfunction "1_1") (pintype "passive"))
      (node (ref "C125") (pin "1") (pinfunction "1_1") (pintype "passive"))
      (node (ref "C126") (pin "1") (pinfunction "1_1") (pintype "passive"))
      (node (ref "C127") (pin "1") (pinfunction "1_1") (pintype "passive"))
      (node (ref "C128") (pin "1") (pinfunction "1_1") (pintype "passive"))
      (node (ref "C129") (pin "1") (pinfunction "1_1") (pintype "passive"))
      (node (ref "C130") (pin "1") (pinfunction "1_1") (pintype "passive"))
      (node (ref "C131") (pin "1") (pinfunction "1_1") (pintype "passive"))
      (node (ref "C132") (pin "1") (pinfunction "1_1") (pintype "passive"))
      (node (ref "C133") (pin "1") (pinfunction "1_1") (pintype "passive"))
      (node (ref "C134") (pin "1") (pinfunction "1_1") (pintype "passive"))
      (node (ref "C145") (pin "1") (pinfunction "1_1") (pintype "passive"))
      (node (ref "C146") (pin "1") (pinfunction "1_1") (pintype "passive"))
      (node (ref "C147") (pin "1") (pinfunction "1_1") (pintype "passive"))
      (node (ref "C148") (pin "1") (pinfunction "1_1") (pintype "passive"))
      (node (ref "C149") (pin "1") (pinfunction "1_1") (pintype "passive"))
      (node (ref "C160") (pin "1") (pinfunction "1_1") (pintype "passive"))
      (node (ref "C161") (pin "1") (pinfunction "1_1") (pintype "passive"))
      (node (ref "C162") (pin "1") (pinfunction "1_1") (pintype "passive"))
      (node (ref "C163") (pin "1") (pinfunction "1_1") (pintype "passive"))
      (node (ref "U1") (pin "G8") (pinfunction "VCCPINT_G8") (pintype "power_in"))
      (node (ref "U1") (pin "H11") (pinfunction "VCCBRAM_H11") (pintype "power_in"))
      (node (ref "U1") (pin "H9") (pinfunction "VCCPINT_H9") (pintype "power_in"))
      (node (ref "U1") (pin "J10") (pinfunction "VCCBRAM_J10") (pintype "power_in"))
      (node (ref "U1") (pin "J12") (pinfunction "VCCINT_J12") (pintype "power_in"))
      (node (ref "U1") (pin "J14") (pinfunction "VCCINT_J14") (pintype "power_in"))
      (node (ref "U1") (pin "J8") (pinfunction "VCCPINT_J8") (pintype "power_in"))
      (node (ref "U1") (pin "K13") (pinfunction "VCCINT_K13") (pintype "power_in"))
      (node (ref "U1") (pin "L14") (pinfunction "VCCINT_L14") (pintype "power_in"))
      (node (ref "U1") (pin "L8") (pinfunction "VCCPINT_L8") (pintype "power_in"))
      (node (ref "U1") (pin "M13") (pinfunction "VCCINT_M13") (pintype "power_in"))
      (node (ref "U1") (pin "N14") (pinfunction "VCCINT_N14") (pintype "power_in"))
      (node (ref "U1") (pin "N8") (pinfunction "VCCPINT_N8") (pintype "power_in"))
      (node (ref "U1") (pin "P13") (pinfunction "VCCINT_P13") (pintype "power_in"))
      (node (ref "U1") (pin "R14") (pinfunction "VCCINT_R14") (pintype "power_in"))
      (node (ref "U1") (pin "R8") (pinfunction "VCCPINT_R8") (pintype "power_in"))
    )
    (net (code "2") (name "1.5V") (class "Default")
      (node (ref "C153") (pin "1") (pinfunction "1_1") (pintype "passive"))
      (node (ref "C154") (pin "1") (pinfunction "1_1") (pintype "passive"))
      (node (ref "C155") (pin "1") (pinfunction "1_1") (pintype "passive"))
      (node (ref "C156") (pin "1") (pinfunction "1_1") (pintype "passive"))
      (node (ref "C157") (pin "1") (pinfunction "1_1") (pintype "passive"))
      (node (ref "C158") (pin "1") (pinfunction "1_1") (pintype "passive"))
      (node (ref "C167") (pin "1") (pinfunction "1_1") (pintype "passive"))
      (node (ref "C168") (pin "1") (pinfunction "1_1") (pintype "passive"))
      (node (ref "C169") (pin "1") (pinfunction "1_1") (pintype "passive"))
      (node (ref "C170") (pin "1") (pinfunction "1_1") (pintype "passive"))
      (node (ref "C171") (pin "1") (pinfunction "1_1") (pintype "passive"))
      (node (ref "U1") (pin "E2") (pinfunction "VCCO_DDR_502_E2") (pintype "power_in"))
      (node (ref "U1") (pin "F5") (pinfunction "VCCO_DDR_502_F5") (pintype "power_in"))
      (node (ref "U1") (pin "H1") (pinfunction "VCCO_DDR_502_H1") (pintype "power_in"))
      (node (ref "U1") (pin "J4") (pinfunction "VCCO_DDR_502_J4") (pintype "power_in"))
      (node (ref "U1") (pin "K7") (pinfunction "VCCO_DDR_502_K7") (pintype "power_in"))
      (node (ref "U1") (pin "M3") (pinfunction "VCCO_DDR_502_M3") (pintype "power_in"))
      (node (ref "U1") (pin "N6") (pinfunction "VCCO_DDR_502_N6") (pintype "power_in"))
      (node (ref "U1") (pin "R2") (pinfunction "VCCO_DDR_502_R2") (pintype "power_in"))
      (node (ref "U1") (pin "V1") (pinfunction "VCCO_DDR_502_V1") (pintype "power_in"))
    )
    (net (code "3") (name "1.8V") (class "Default")
      (node (ref "C113") (pin "1") (pinfunction "1_1") (pintype "passive"))
      (node (ref "C114") (pin "1") (pinfunction "1_1") (pintype "passive"))
      (node (ref "C115") (pin "1") (pinfunction "1_1") (pintype "passive"))
      (node (ref "C116") (pin "1") (pinfunction "1_1") (pintype "passive"))
      (node (ref "C150") (pin "1") (pinfunction "1_1") (pintype "passive"))
      (node (ref "C151") (pin "1") (pinfunction "1_1") (pintype "passive"))
      (node (ref "C152") (pin "1") (pinfunction "1_1") (pintype "passive"))
      (node (ref "C164") (pin "1") (pinfunction "1_1") (pintype "passive"))
      (node (ref "C165") (pin "1") (pinfunction "1_1") (pintype "passive"))
      (node (ref "C166") (pin "1") (pinfunction "1_1") (pintype "passive"))
      (node (ref "C73") (pin "1") (pinfunction "1_1") (pintype "passive"))
      (node (ref "L3") (pin "2") (pinfunction "2_2") (pintype "passive"))
      (node (ref "L4") (pin "2") (pinfunction "2_2") (pintype "passive"))
      (node (ref "U1") (pin "G9") (pinfunction "VCCBATT_0_G9") (pintype "power_in"))
      (node (ref "U1") (pin "K9") (pinfunction "VCCPAUX_K9") (pintype "power_in"))
      (node (ref "U1") (pin "L10") (pinfunction "VCCAUX_L10") (pintype "power_in"))
      (node (ref "U1") (pin "M9") (pinfunction "VCCPAUX_M9") (pintype "power_in"))
      (node (ref "U1") (pin "N10") (pinfunction "VCCAUX_N10") (pintype "power_in"))
      (node (ref "U1") (pin "P11") (pinfunction "VCCAUX_P11") (pintype "power_in"))
      (node (ref "U1") (pin "P9") (pinfunction "VCCPAUX_P9") (pintype "power_in"))
      (node (ref "U1") (pin "R10") (pinfunction "VCCAUX_R10") (pintype "power_in"))
      (node (ref "U1") (pin "T9") (pinfunction "VCCPAUX_T9") (pintype "power_in"))
    )
    (net (code "4") (name "1.8VADC") (class "Default")
      (node (ref "C74") (pin "1") (pinfunction "1_1") (pintype "passive"))
      (node (ref "C75") (pin "1") (pinfunction "1_1") (pintype "passive"))
      (node (ref "L4") (pin "1") (pinfunction "1_1") (pintype "passive"))
      (node (ref "U1") (pin "K11") (pinfunction "VCCADC_0_K11") (pintype "power_in"))
    )
    (net (code "5") (name "1.8VPLL") (class "Default")
      (node (ref "C260") (pin "1") (pinfunction "1_1") (pintype "passive"))
      (node (ref "C72") (pin "1") (pinfunction "1_1") (pintype "passive"))
      (node (ref "L3") (pin "1") (pinfunction "1_1") (pintype "passive"))
      (node (ref "U1") (pin "H10") (pinfunction "VCCPLL_H10") (pintype "power_in"))
    )
    (net (code "6") (name "3.3V") (class "Default")
      (node (ref "C159") (pin "1") (pinfunction "1_1") (pintype "passive"))
      (node (ref "C84") (pin "1") (pinfunction "1_1") (pintype "passive"))
      (node (ref "C85") (pin "1") (pinfunction "1_1") (pintype "passive"))
      (node (ref "C86") (pin "1") (pinfunction "1_1") (pintype "passive"))
      (node (ref "C87") (pin "1") (pinfunction "1_1") (pintype "passive"))
      (node (ref "C88") (pin "1") (pinfunction "1_1") (pintype "passive"))
      (node (ref "C89") (pin "1") (pinfunction "1_1") (pintype "passive"))
      (node (ref "C90") (pin "1") (pinfunction "1_1") (pintype "passive"))
      (node (ref "C91") (pin "1") (pinfunction "1_1") (pintype "passive"))
      (node (ref "U1") (pin "A10") (pinfunction "VCCO_MIO1_501_A10") (pintype "power_in"))
      (node (ref "U1") (pin "B13") (pinfunction "VCCO_MIO1_501_B13") (pintype "power_in"))
      (node (ref "U1") (pin "B3") (pinfunction "VCCO_MIO0_500_B3") (pintype "power_in"))
      (node (ref "U1") (pin "C6") (pinfunction "VCCO_MIO0_500_C6") (pintype "power_in"))
      (node (ref "U1") (pin "D9") (pinfunction "VCCO_MIO1_501_D9") (pintype "power_in"))
      (node (ref "U1") (pin "E12") (pinfunction "VCCO_MIO1_501_E12") (pintype "power_in"))
      (node (ref "U1") (pin "R12") (pinfunction "VCCO_0_R12") (pintype "power_in"))
      (node (ref "U1") (pin "T10") (pinfunction "RSVDVCC3_T10") (pintype "power_in"))
      (node (ref "U1") (pin "T7") (pinfunction "RSVDVCC1_T7") (pintype "power_in"))
      (node (ref "U1") (pin "T8") (pinfunction "RSVDVCC2_T8") (pintype "power_in"))
    )
    (net (code "7") (name "GND") (class "Default")
      (node (ref "C100") (pin "2") (pinfunction "2_2") (pintype "passive"))
      (node (ref "C101") (pin "2") (pinfunction "2_2") (pintype "passive"))
      (node (ref "C102") (pin "2") (pinfunction "2_2") (pintype "passive"))
      (node (ref "C103") (pin "2") (pinfunction "2_2") (pintype "passive"))
      (node (ref "C104") (pin "2") (pinfunction "2_2") (pintype "passive"))
      (node (ref "C105") (pin "2") (pinfunction "2_2") (pintype "passive"))
      (node (ref "C106") (pin "2") (pinfunction "2_2") (pintype "passive"))
      (node (ref "C107") (pin "2") (pinfunction "2_2") (pintype "passive"))
      (node (ref "C108") (pin "2") (pinfunction "2_2") (pintype "passive"))
      (node (ref "C109") (pin "2") (pinfunction "2_2") (pintype "passive"))
      (node (ref "C110") (pin "2") (pinfunction "2_2") (pintype "passive"))
      (node (ref "C111") (pin "2") (pinfunction "2_2") (pintype "passive"))
      (node (ref "C112") (pin "2") (pinfunction "2_2") (pintype "passive"))
      (node (ref "C113") (pin "2") (pinfunction "2_2") (pintype "passive"))
      (node (ref "C114") (pin "2") (pinfunction "2_2") (pintype "passive"))
      (node (ref "C115") (pin "2") (pinfunction "2_2") (pintype "passive"))
      (node (ref "C116") (pin "2") (pinfunction "2_2") (pintype "passive"))
      (node (ref "C117") (pin "2") (pinfunction "2_2") (pintype "passive"))
      (node (ref "C118") (pin "2") (pinfunction "2_2") (pintype "passive"))
      (node (ref "C119") (pin "2") (pinfunction "2_2") (pintype "passive"))
      (node (ref "C120") (pin "2") (pinfunction "2_2") (pintype "passive"))
      (node (ref "C121") (pin "2") (pinfunction "2_2") (pintype "passive"))
      (node (ref "C122") (pin "2") (pinfunction "2_2") (pintype "passive"))
      (node (ref "C123") (pin "2") (pinfunction "2_2") (pintype "passive"))
      (node (ref "C124") (pin "2") (pinfunction "2_2") (pintype "passive"))
      (node (ref "C125") (pin "2") (pinfunction "2_2") (pintype "passive"))
      (node (ref "C126") (pin "2") (pinfunction "2_2") (pintype "passive"))
      (node (ref "C127") (pin "2") (pinfunction "2_2") (pintype "passive"))
      (node (ref "C128") (pin "2") (pinfunction "2_2") (pintype "passive"))
      (node (ref "C129") (pin "2") (pinfunction "2_2") (pintype "passive"))
      (node (ref "C130") (pin "2") (pinfunction "2_2") (pintype "passive"))
      (node (ref "C131") (pin "2") (pinfunction "2_2") (pintype "passive"))
      (node (ref "C132") (pin "2") (pinfunction "2_2") (pintype "passive"))
      (node (ref "C133") (pin "2") (pinfunction "2_2") (pintype "passive"))
      (node (ref "C134") (pin "2") (pinfunction "2_2") (pintype "passive"))
      (node (ref "C135") (pin "2") (pinfunction "2_2") (pintype "passive"))
      (node (ref "C136") (pin "2") (pinfunction "2_2") (pintype "passive"))
      (node (ref "C137") (pin "2") (pinfunction "2_2") (pintype "passive"))
      (node (ref "C138") (pin "2") (pinfunction "2_2") (pintype "passive"))
      (node (ref "C139") (pin "2") (pinfunction "2_2") (pintype "passive"))
      (node (ref "C140") (pin "2") (pinfunction "2_2") (pintype "passive"))
      (node (ref "C141") (pin "2") (pinfunction "2_2") (pintype "passive"))
      (node (ref "C142") (pin "2") (pinfunction "2_2") (pintype "passive"))
      (node (ref "C143") (pin "2") (pinfunction "2_2") (pintype "passive"))
      (node (ref "C144") (pin "2") (pinfunction "2_2") (pintype "passive"))
      (node (ref "C145") (pin "2") (pinfunction "2_2") (pintype "passive"))
      (node (ref "C146") (pin "2") (pinfunction "2_2") (pintype "passive"))
      (node (ref "C147") (pin "2") (pinfunction "2_2") (pintype "passive"))
      (node (ref "C148") (pin "2") (pinfunction "2_2") (pintype "passive"))
      (node (ref "C149") (pin "2") (pinfunction "2_2") (pintype "passive"))
      (node (ref "C150") (pin "2") (pinfunction "2_2") (pintype "passive"))
      (node (ref "C151") (pin "2") (pinfunction "2_2") (pintype "passive"))
      (node (ref "C152") (pin "2") (pinfunction "2_2") (pintype "passive"))
      (node (ref "C153") (pin "2") (pinfunction "2_2") (pintype "passive"))
      (node (ref "C154") (pin "2") (pinfunction "2_2") (pintype "passive"))
      (node (ref "C155") (pin "2") (pinfunction "2_2") (pintype "passive"))
      (node (ref "C156") (pin "2") (pinfunction "2_2") (pintype "passive"))
      (node (ref "C157") (pin "2") (pinfunction "2_2") (pintype "passive"))
      (node (ref "C158") (pin "2") (pinfunction "2_2") (pintype "passive"))
      (node (ref "C159") (pin "2") (pinfunction "2_2") (pintype "passive"))
      (node (ref "C160") (pin "2") (pinfunction "2_2") (pintype "passive"))
      (node (ref "C161") (pin "2") (pinfunction "2_2") (pintype "passive"))
      (node (ref "C162") (pin "2") (pinfunction "2_2") (pintype "passive"))
      (node (ref "C163") (pin "2") (pinfunction "2_2") (pintype "passive"))
      (node (ref "C164") (pin "2") (pinfunction "2_2") (pintype "passive"))
      (node (ref "C165") (pin "2") (pinfunction "2_2") (pintype "passive"))
      (node (ref "C166") (pin "2") (pinfunction "2_2") (pintype "passive"))
      (node (ref "C167") (pin "2") (pinfunction "2_2") (pintype "passive"))
      (node (ref "C168") (pin "2") (pinfunction "2_2") (pintype "passive"))
      (node (ref "C169") (pin "2") (pinfunction "2_2") (pintype "passive"))
      (node (ref "C170") (pin "2") (pinfunction "2_2") (pintype "passive"))
      (node (ref "C171") (pin "2") (pinfunction "2_2") (pintype "passive"))
      (node (ref "C260") (pin "2") (pinfunction "2_2") (pintype "passive"))
      (node (ref "C72") (pin "2") (pinfunction "2_2") (pintype "passive"))
      (node (ref "C73") (pin "2") (pinfunction "2_2") (pintype "passive"))
      (node (ref "C74") (pin "2") (pinfunction "2_2") (pintype "passive"))
      (node (ref "C75") (pin "2") (pinfunction "2_2") (pintype "passive"))
      (node (ref "C76") (pin "2") (pinfunction "2_2") (pintype "passive"))
      (node (ref "C77") (pin "2") (pinfunction "2_2") (pintype "passive"))
      (node (ref "C78") (pin "2") (pinfunction "2_2") (pintype "passive"))
      (node (ref "C79") (pin "2") (pinfunction "2_2") (pintype "passive"))
      (node (ref "C80") (pin "2") (pinfunction "2_2") (pintype "passive"))
      (node (ref "C81") (pin "2") (pinfunction "2_2") (pintype "passive"))
      (node (ref "C82") (pin "2") (pinfunction "2_2") (pintype "passive"))
      (node (ref "C83") (pin "2") (pinfunction "2_2") (pintype "passive"))
      (node (ref "C84") (pin "2") (pinfunction "2_2") (pintype "passive"))
      (node (ref "C85") (pin "2") (pinfunction "2_2") (pintype "passive"))
      (node (ref "C86") (pin "2") (pinfunction "2_2") (pintype "passive"))
      (node (ref "C87") (pin "2") (pinfunction "2_2") (pintype "passive"))
      (node (ref "C88") (pin "2") (pinfunction "2_2") (pintype "passive"))
      (node (ref "C89") (pin "2") (pinfunction "2_2") (pintype "passive"))
      (node (ref "C90") (pin "2") (pinfunction "2_2") (pintype "passive"))
      (node (ref "C91") (pin "2") (pinfunction "2_2") (pintype "passive"))
      (node (ref "C92") (pin "2") (pinfunction "2_2") (pintype "passive"))
      (node (ref "C93") (pin "2") (pinfunction "2_2") (pintype "passive"))
      (node (ref "C94") (pin "2") (pinfunction "2_2") (pintype "passive"))
      (node (ref "C95") (pin "2") (pinfunction "2_2") (pintype "passive"))
      (node (ref "C96") (pin "2") (pinfunction "2_2") (pintype "passive"))
      (node (ref "C97") (pin "2") (pinfunction "2_2") (pintype "passive"))
      (node (ref "C98") (pin "2") (pinfunction "2_2") (pintype "passive"))
      (node (ref "C99") (pin "2") (pinfunction "2_2") (pintype "passive"))
      (node (ref "U1") (pin "A15") (pinfunction "GND_A15") (pintype "power_in"))
      (node (ref "U1") (pin "A5") (pinfunction "GND_A5") (pintype "power_in"))
      (node (ref "U1") (pin "AA15") (pinfunction "GND_AA15") (pintype "power_in"))
      (node (ref "U1") (pin "AA5") (pinfunction "GND_AA5") (pintype "power_in"))
      (node (ref "U1") (pin "AB18") (pinfunction "GND_AB18") (pintype "power_in"))
      (node (ref "U1") (pin "AB8") (pinfunction "GND_AB8") (pintype "power_in"))
      (node (ref "U1") (pin "B18") (pinfunction "GND_B18") (pintype "power_in"))
      (node (ref "U1") (pin "B8") (pinfunction "GND_B8") (pintype "power_in"))
      (node (ref "U1") (pin "C1") (pinfunction "GND_C1") (pintype "power_in"))
      (node (ref "U1") (pin "C11") (pinfunction "GND_C11") (pintype "power_in"))
      (node (ref "U1") (pin "C21") (pinfunction "GND_C21") (pintype "power_in"))
      (node (ref "U1") (pin "D14") (pinfunction "GND_D14") (pintype "power_in"))
      (node (ref "U1") (pin "D4") (pinfunction "GND_D4") (pintype "power_in"))
      (node (ref "U1") (pin "E17") (pinfunction "GND_E17") (pintype "power_in"))
      (node (ref "U1") (pin "E7") (pinfunction "GND_E7") (pintype "power_in"))
      (node (ref "U1") (pin "F10") (pinfunction "GND_F10") (pintype "power_in"))
      (node (ref "U1") (pin "F20") (pinfunction "GND_F20") (pintype "power_in"))
      (node (ref "U1") (pin "G10") (pinfunction "RSVDGND_G10") (pintype "power_in"))
      (node (ref "U1") (pin "G3") (pinfunction "GND_G3") (pintype "power_in"))
      (node (ref "U1") (pin "H12") (pinfunction "GND_H12") (pintype "power_in"))
      (node (ref "U1") (pin "H14") (pinfunction "GND_H14") (pintype "power_in"))
      (node (ref "U1") (pin "H16") (pinfunction "GND_H16") (pintype "power_in"))
      (node (ref "U1") (pin "H6") (pinfunction "GND_H6") (pintype "power_in"))
      (node (ref "U1") (pin "H8") (pinfunction "GND_H8") (pintype "power_in"))
      (node (ref "U1") (pin "J11") (pinfunction "GND_J11") (pintype "power_in"))
      (node (ref "U1") (pin "J13") (pinfunction "GND_J13") (pintype "power_in"))
      (node (ref "U1") (pin "J19") (pinfunction "GND_J19") (pintype "power_in"))
      (node (ref "U1") (pin "J9") (pinfunction "GND_J9") (pintype "power_in"))
      (node (ref "U1") (pin "K10") (pinfunction "GND_K10") (pintype "power_in"))
      (node (ref "U1") (pin "K12") (pinfunction "GNDADC_0_K12") (pintype "power_in"))
      (node (ref "U1") (pin "K14") (pinfunction "GND_K14") (pintype "power_in"))
      (node (ref "U1") (pin "K2") (pinfunction "GND_K2") (pintype "power_in"))
      (node (ref "U1") (pin "K22") (pinfunction "GND_K22") (pintype "power_in"))
      (node (ref "U1") (pin "K8") (pinfunction "GND_K8") (pintype "power_in"))
      (node (ref "U1") (pin "L13") (pinfunction "GND_L13") (pintype "power_in"))
      (node (ref "U1") (pin "L15") (pinfunction "GND_L15") (pintype "power_in"))
      (node (ref "U1") (pin "L5") (pinfunction "GND_L5") (pintype "power_in"))
      (node (ref "U1") (pin "L9") (pinfunction "GND_L9") (pintype "power_in"))
      (node (ref "U1") (pin "M10") (pinfunction "GND_M10") (pintype "power_in"))
      (node (ref "U1") (pin "M14") (pinfunction "GND_M14") (pintype "power_in"))
      (node (ref "U1") (pin "M18") (pinfunction "GND_M18") (pintype "power_in"))
      (node (ref "U1") (pin "M8") (pinfunction "GND_M8") (pintype "power_in"))
      (node (ref "U1") (pin "N1") (pinfunction "GND_N1") (pintype "power_in"))
      (node (ref "U1") (pin "N13") (pinfunction "GND_N13") (pintype "power_in"))
      (node (ref "U1") (pin "N21") (pinfunction "GND_N21") (pintype "power_in"))
      (node (ref "U1") (pin "N9") (pinfunction "GND_N9") (pintype "power_in"))
      (node (ref "U1") (pin "P10") (pinfunction "GND_P10") (pintype "power_in"))
      (node (ref "U1") (pin "P12") (pinfunction "GND_P12") (pintype "power_in"))
      (node (ref "U1") (pin "P14") (pinfunction "GND_P14") (pintype "power_in"))
      (node (ref "U1") (pin "P4") (pinfunction "GND_P4") (pintype "power_in"))
      (node (ref "U1") (pin "P8") (pinfunction "GND_P8") (pintype "power_in"))
      (node (ref "U1") (pin "R11") (pinfunction "GND_R11") (pintype "power_in"))
      (node (ref "U1") (pin "R13") (pinfunction "GND_R13") (pintype "power_in"))
      (node (ref "U1") (pin "R17") (pinfunction "GND_R17") (pintype "power_in"))
      (node (ref "U1") (pin "R9") (pinfunction "GND_R9") (pintype "power_in"))
      (node (ref "U1") (pin "T20") (pinfunction "GND_T20") (pintype "power_in"))
      (node (ref "U1") (pin "U13") (pinfunction "GND_U13") (pintype "power_in"))
      (node (ref "U1") (pin "U3") (pinfunction "GND_U3") (pintype "power_in"))
      (node (ref "U1") (pin "V16") (pinfunction "GND_V16") (pintype "power_in"))
      (node (ref "U1") (pin "V6") (pinfunction "GND_V6") (pintype "power_in"))
      (node (ref "U1") (pin "W19") (pinfunction "GND_W19") (pintype "power_in"))
      (node (ref "U1") (pin "W9") (pinfunction "GND_W9") (pintype "power_in"))
      (node (ref "U1") (pin "Y12") (pinfunction "GND_Y12") (pintype "power_in"))
      (node (ref "U1") (pin "Y2") (pinfunction "GND_Y2") (pintype "power_in"))
      (node (ref "U1") (pin "Y22") (pinfunction "GND_Y22") (pintype "power_in"))
    )
    (net (code "8") (name "VCCO_13") (class "Default")
      (node (ref "C76") (pin "1") (pinfunction "1_1") (pintype "passive"))
      (node (ref "C77") (pin "1") (pinfunction "1_1") (pintype "passive"))
      (node (ref "C78") (pin "1") (pinfunction "1_1") (pintype "passive"))
      (node (ref "C79") (pin "1") (pinfunction "1_1") (pintype "passive"))
      (node (ref "C92") (pin "1") (pinfunction "1_1") (pintype "passive"))
      (node (ref "C93") (pin "1") (pinfunction "1_1") (pintype "passive"))
      (node (ref "C94") (pin "1") (pinfunction "1_1") (pintype "passive"))
      (node (ref "C95") (pin "1") (pinfunction "1_1") (pintype "passive"))
      (node (ref "C96") (pin "1") (pinfunction "1_1") (pintype "passive"))
      (node (ref "U1") (pin "AA10") (pinfunction "VCCO_13_AA10") (pintype "power_in"))
      (node (ref "U1") (pin "AB3") (pinfunction "VCCO_13_AB3") (pintype "power_in"))
      (node (ref "U1") (pin "T5") (pinfunction "VCCO_13_T5") (pintype "power_in"))
      (node (ref "U1") (pin "U8") (pinfunction "VCCO_13_U8") (pintype "power_in"))
      (node (ref "U1") (pin "V11") (pinfunction "VCCO_13_V11") (pintype "power_in"))
      (node (ref "U1") (pin "W4") (pinfunction "VCCO_13_W4") (pintype "power_in"))
      (node (ref "U1") (pin "Y7") (pinfunction "VCCO_13_Y7") (pintype "power_in"))
    )
    (net (code "9") (name "VCCO_33") (class "Default")
      (node (ref "C117") (pin "1") (pinfunction "1_1") (pintype "passive"))
      (node (ref "C118") (pin "1") (pinfunction "1_1") (pintype "passive"))
      (node (ref "C119") (pin "1") (pinfunction "1_1") (pintype "passive"))
      (node (ref "C120") (pin "1") (pinfunction "1_1") (pintype "passive"))
      (node (ref "C135") (pin "1") (pinfunction "1_1") (pintype "passive"))
      (node (ref "C136") (pin "1") (pinfunction "1_1") (pintype "passive"))
      (node (ref "C137") (pin "1") (pinfunction "1_1") (pintype "passive"))
      (node (ref "C138") (pin "1") (pinfunction "1_1") (pintype "passive"))
      (node (ref "C139") (pin "1") (pinfunction "1_1") (pintype "passive"))
      (node (ref "U1") (pin "AA20") (pinfunction "VCCO_33_AA20") (pintype "power_in"))
      (node (ref "U1") (pin "AB13") (pinfunction "VCCO_33_AB13") (pintype "power_in"))
      (node (ref "U1") (pin "U18") (pinfunction "VCCO_33_U18") (pintype "power_in"))
      (node (ref "U1") (pin "V21") (pinfunction "VCCO_33_V21") (pintype "power_in"))
      (node (ref "U1") (pin "W14") (pinfunction "VCCO_33_W14") (pintype "power_in"))
      (node (ref "U1") (pin "Y17") (pinfunction "VCCO_33_Y17") (pintype "power_in"))
    )
    (net (code "10") (name "VCCO_34") (class "Default")
      (node (ref "C100") (pin "1") (pinfunction "1_1") (pintype "passive"))
      (node (ref "C101") (pin "1") (pinfunction "1_1") (pintype "passive"))
      (node (ref "C80") (pin "1") (pinfunction "1_1") (pintype "passive"))
      (node (ref "C81") (pin "1") (pinfunction "1_1") (pintype "passive"))
      (node (ref "C82") (pin "1") (pinfunction "1_1") (pintype "passive"))
      (node (ref "C83") (pin "1") (pinfunction "1_1") (pintype "passive"))
      (node (ref "C97") (pin "1") (pinfunction "1_1") (pintype "passive"))
      (node (ref "C98") (pin "1") (pinfunction "1_1") (pintype "passive"))
      (node (ref "C99") (pin "1") (pinfunction "1_1") (pintype "passive"))
      (node (ref "U1") (pin "K17") (pinfunction "VCCO_34_K17") (pintype "power_in"))
      (node (ref "U1") (pin "L20") (pinfunction "VCCO_34_L20") (pintype "power_in"))
      (node (ref "U1") (pin "N16") (pinfunction "VCCO_34_N16") (pintype "power_in"))
      (node (ref "U1") (pin "P19") (pinfunction "VCCO_34_P19") (pintype "power_in"))
      (node (ref "U1") (pin "R22") (pinfunction "VCCO_34_R22") (pintype "power_in"))
      (node (ref "U1") (pin "T15") (pinfunction "VCCO_34_T15") (pintype "power_in"))
    )
    (net (code "11") (name "VCCO_35") (class "Default")
      (node (ref "C121") (pin "1") (pinfunction "1_1") (pintype "passive"))
      (node (ref "C122") (pin "1") (pinfunction "1_1") (pintype "passive"))
      (node (ref "C123") (pin "1") (pinfunction "1_1") (pintype "passive"))
      (node (ref "C124") (pin "1") (pinfunction "1_1") (pintype "passive"))
      (node (ref "C140") (pin "1") (pinfunction "1_1") (pintype "passive"))
      (node (ref "C141") (pin "1") (pinfunction "1_1") (pintype "passive"))
      (node (ref "C142") (pin "1") (pinfunction "1_1") (pintype "passive"))
      (node (ref "C143") (pin "1") (pinfunction "1_1") (pintype "passive"))
      (node (ref "C144") (pin "1") (pinfunction "1_1") (pintype "passive"))
      (node (ref "U1") (pin "A20") (pinfunction "VCCO_35_A20") (pintype "power_in"))
      (node (ref "U1") (pin "C16") (pinfunction "VCCO_35_C16") (pintype "power_in"))
      (node (ref "U1") (pin "D19") (pinfunction "VCCO_35_D19") (pintype "power_in"))
      (node (ref "U1") (pin "E22") (pinfunction "VCCO_35_E22") (pintype "power_in"))
      (node (ref "U1") (pin "F15") (pinfunction "VCCO_35_F15") (pintype "power_in"))
      (node (ref "U1") (pin "G18") (pinfunction "VCCO_35_G18") (pintype "power_in"))
      (node (ref "U1") (pin "H21") (pinfunction "VCCO_35_H21") (pintype "power_in"))
    )
  )
)
